# CAN_TO_USART_V2_1.net
KiCad netlist of a schematic drawn in Altium Designer
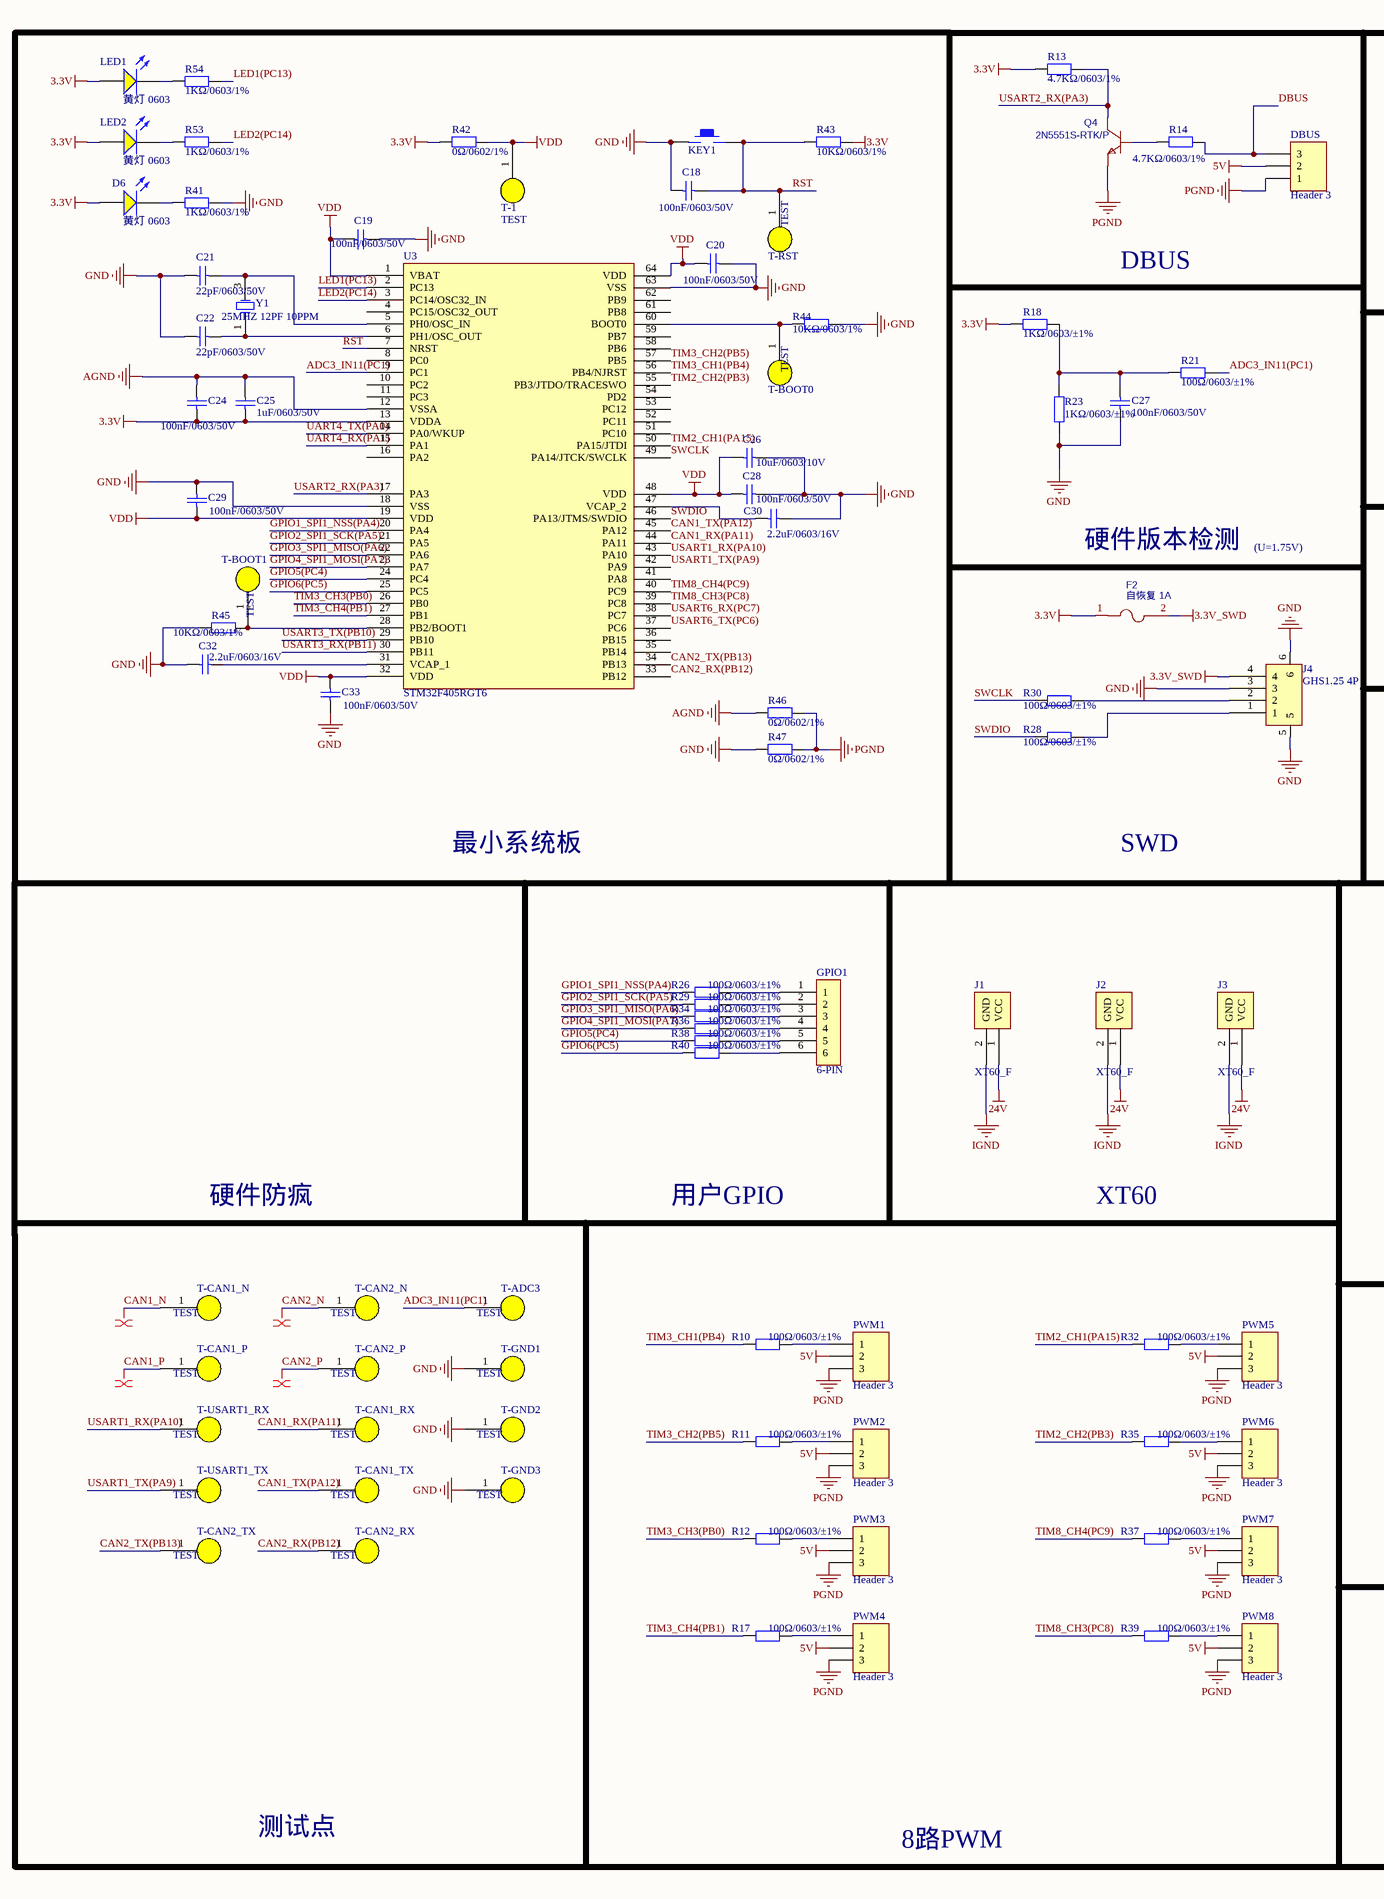
[diagram p0: CAN_TO_USART_V2.1.SchDoc, left]
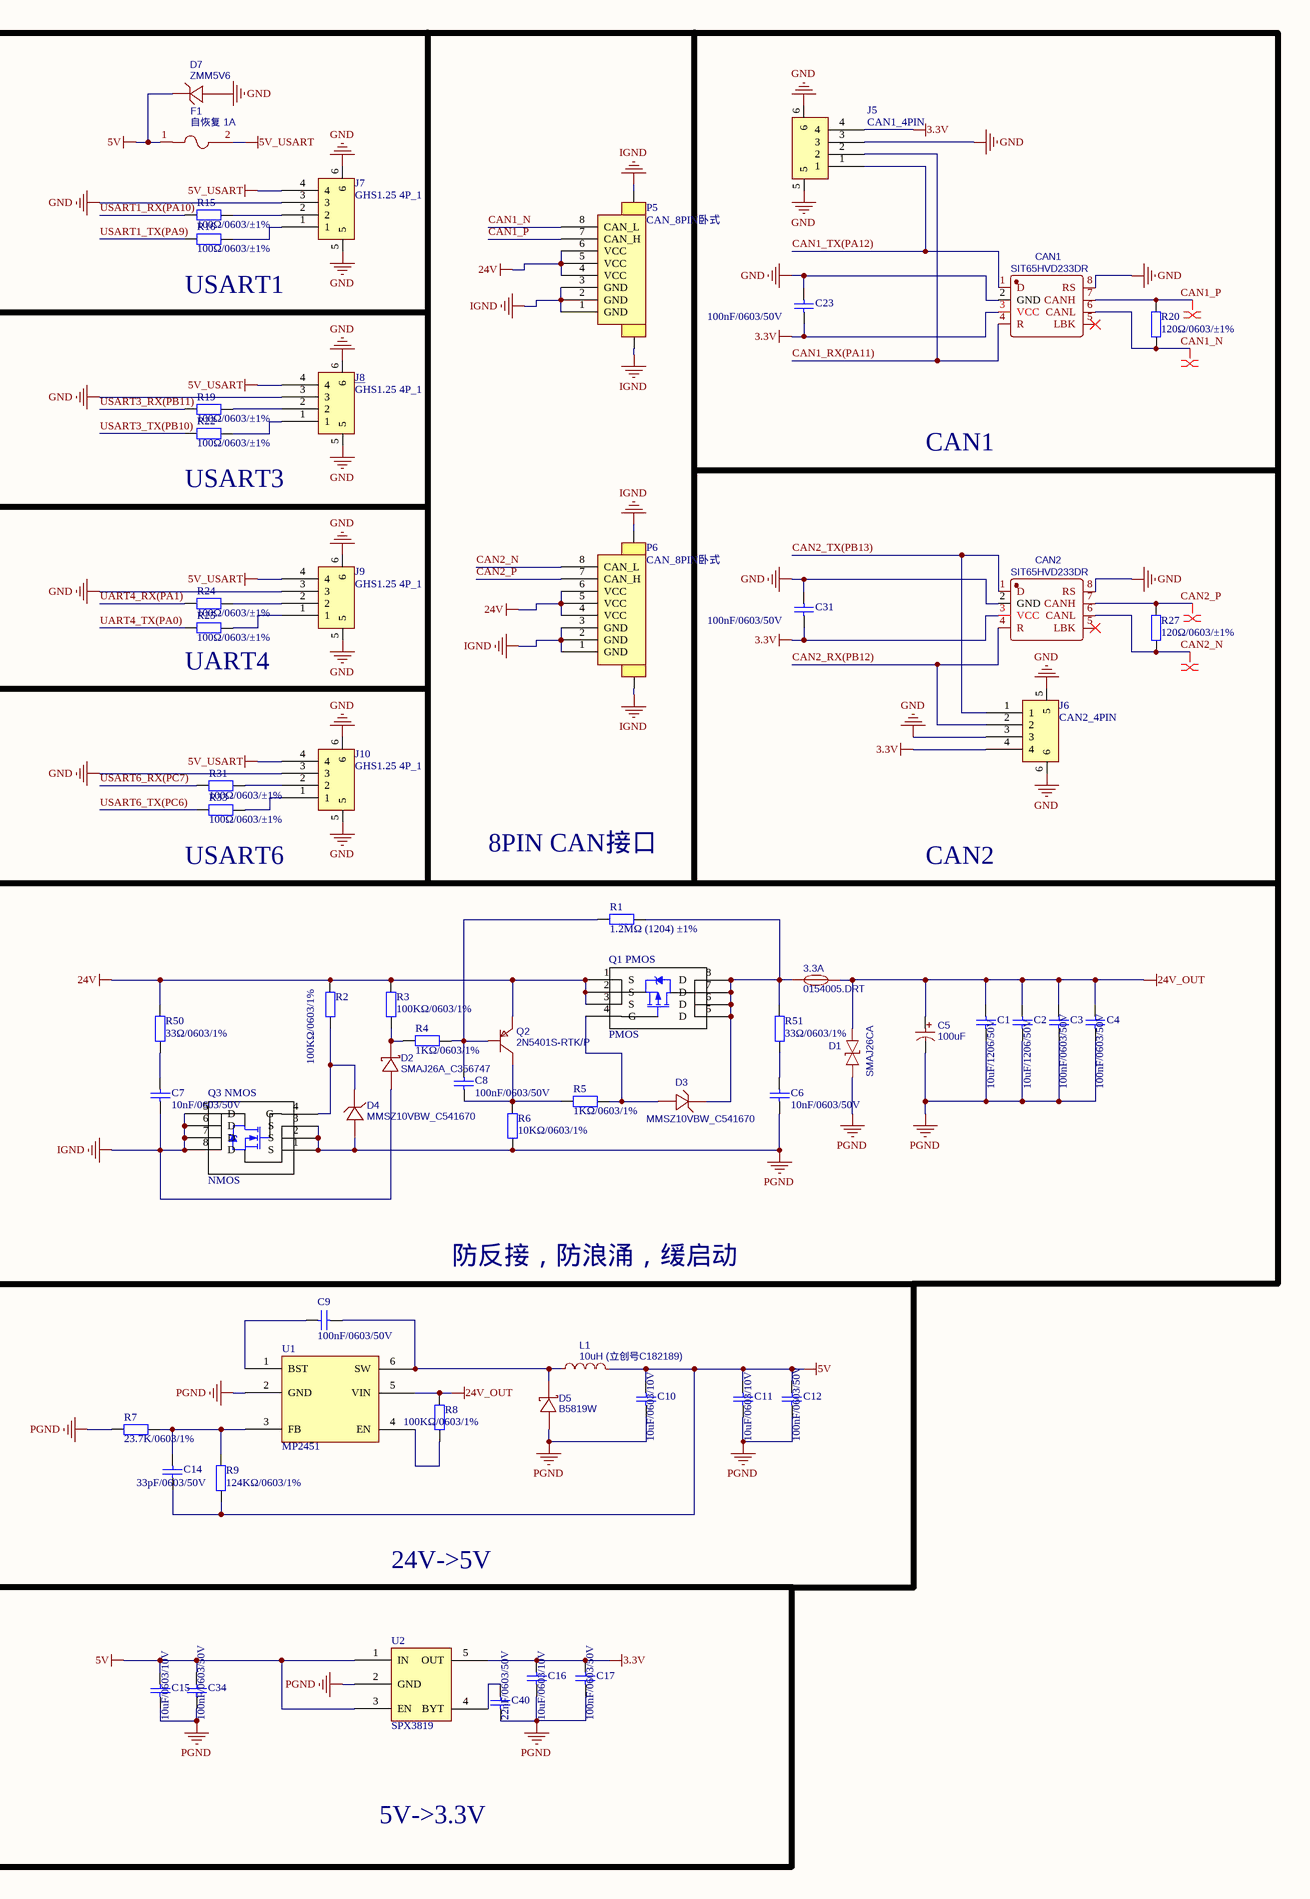
[diagram p1: CAN_TO_USART_V2.1.SchDoc, right]

(export (version "E")
  (design (tool "Eeschema 10.0.6"))
  (components
    (comp (ref "3.3A")
      (value "0154005.DRT")
      (footprint "FUSE 3.3A")
      (fields (field (name "BOM_SUPPLIER PART") "C206917") (field (name "CONTRIBUTOR") "LCSC"))
      (libsource (lib "altium-import") (part "root_0_mirrored_0154005.DRT_"))
    )
    (comp (ref "C1")
      (value "10uF/1206/50V")
      (footprint "1206_C")
      (description "贴片电容")
      (libsource (lib "Miscellaneous Devices LC") (part "1206 10uF (106) 10% 50V"))
    )
    (comp (ref "C2")
      (value "10uF/1206/50V")
      (footprint "1206_C")
      (description "贴片电容")
      (libsource (lib "Miscellaneous Devices LC") (part "1206 10uF (106) 10% 50V"))
    )
    (comp (ref "C3")
      (value "100nF/0603/50V")
      (footprint "0603_C")
      (description "贴片电容")
      (libsource (lib "Miscellaneous Devices LC") (part "0603 100nF (104) 10% 50V"))
    )
    (comp (ref "C4")
      (value "100nF/0603/50V")
      (footprint "0603_C")
      (description "贴片电容")
      (libsource (lib "Miscellaneous Devices LC") (part "0603 100nF (104) 10% 50V"))
    )
    (comp (ref "C5")
      (value "100uF")
      (footprint "100UF E")
      (fields
        (field (name "BOM_MANUFACTURER PART") "50V 100uF 8X12")
        (field (name "BOM_SUPPLIER PART") "C2749")
      )
      (libsource (lib "altium-import") (part "root_3_100uF_"))
    )
    (comp (ref "C6")
      (value "10nF/0603/50V")
      (footprint "0603_C")
      (description "贴片电容")
      (libsource (lib "Miscellaneous Devices LC") (part "0603 10nF (103) 10% 50V"))
    )
    (comp (ref "C7")
      (value "10nF/0603/50V")
      (footprint "0603_C")
      (description "贴片电容")
      (libsource (lib "Miscellaneous Devices LC") (part "0603 10nF (103) 10% 50V"))
    )
    (comp (ref "C8")
      (value "100nF/0603/50V")
      (footprint "0603_C")
      (description "贴片电容")
      (libsource (lib "Miscellaneous Devices LC") (part "0603 100nF (104) 10% 50V"))
    )
    (comp (ref "C9")
      (value "100nF/0603/50V")
      (footprint "0603_C")
      (description "贴片电容")
      (libsource (lib "Miscellaneous Devices LC") (part "0603 100nF (104) 10% 50V"))
    )
    (comp (ref "C10")
      (value "10uF/0603/10V")
      (footprint "0603_C")
      (description "贴片电容")
      (libsource (lib "Miscellaneous Devices LC") (part "0603 10uF (106) 10% 10V"))
    )
    (comp (ref "C11")
      (value "10uF/0603/10V")
      (footprint "0603_C")
      (description "贴片电容")
      (libsource (lib "Miscellaneous Devices LC") (part "0603 10uF (106) 10% 10V"))
    )
    (comp (ref "C12")
      (value "100nF/0603/50V")
      (footprint "0603_C")
      (description "贴片电容")
      (libsource (lib "Miscellaneous Devices LC") (part "0603 100nF (104) 10% 50V"))
    )
    (comp (ref "C14")
      (value "33pF/0603/50V")
      (footprint "0603_C")
      (description "贴片电容")
      (libsource (lib "Miscellaneous Devices LC") (part "0603 33pF (330) 5% 50V"))
    )
    (comp (ref "C15")
      (value "10uF/0603/10V")
      (footprint "0603_C")
      (description "贴片电容")
      (libsource (lib "Miscellaneous Devices LC") (part "0603 10uF (106) 10% 10V"))
    )
    (comp (ref "C16")
      (value "10uF/0603/10V")
      (footprint "0603_C")
      (description "贴片电容")
      (libsource (lib "Miscellaneous Devices LC") (part "0603 10uF (106) 10% 10V"))
    )
    (comp (ref "C17")
      (value "100nF/0603/50V")
      (footprint "0603_C")
      (description "贴片电容")
      (libsource (lib "Miscellaneous Devices LC") (part "0603 100nF (104) 10% 50V"))
    )
    (comp (ref "C18")
      (value "100nF/0603/50V")
      (footprint "0603_C")
      (description "贴片电容")
      (libsource (lib "Miscellaneous Devices LC") (part "0603 100nF (104) 10% 50V"))
    )
    (comp (ref "C19")
      (value "100nF/0603/50V")
      (footprint "0603_C")
      (description "贴片电容")
      (libsource (lib "Miscellaneous Devices LC") (part "0603 100nF (104) 10% 50V"))
    )
    (comp (ref "C20")
      (value "100nF/0603/50V")
      (footprint "0603_C")
      (description "贴片电容")
      (libsource (lib "Miscellaneous Devices LC") (part "0603 100nF (104) 10% 50V"))
    )
    (comp (ref "C21")
      (value "22pF/0603/50V")
      (footprint "0603_C")
      (description "贴片电容")
      (libsource (lib "Miscellaneous Devices LC") (part "0603 22pF (220) 5% 50V"))
    )
    (comp (ref "C22")
      (value "22pF/0603/50V")
      (footprint "0603_C")
      (description "贴片电容")
      (libsource (lib "Miscellaneous Devices LC") (part "0603 22pF (220) 5% 50V"))
    )
    (comp (ref "C23")
      (value "100nF/0603/50V")
      (footprint "0603_C")
      (description "贴片电容")
      (libsource (lib "Miscellaneous Devices LC") (part "0603 100nF (104) 10% 50V"))
    )
    (comp (ref "C24")
      (value "100nF/0603/50V")
      (footprint "0603_C")
      (description "贴片电容")
      (libsource (lib "Miscellaneous Devices LC") (part "0603 100nF (104) 10% 50V"))
    )
    (comp (ref "C25")
      (value "1uF/0603/50V")
      (footprint "0603_C")
      (description "贴片电容")
      (libsource (lib "Miscellaneous Devices LC") (part "0603 1uF (105) 10% 50V"))
    )
    (comp (ref "C26")
      (value "10uF/0603/10V")
      (footprint "0603_C")
      (description "贴片电容")
      (libsource (lib "Miscellaneous Devices LC") (part "0603 10uF (106) 10% 10V"))
    )
    (comp (ref "C27")
      (value "100nF/0603/50V")
      (footprint "0603_C")
      (description "贴片电容")
      (libsource (lib "Miscellaneous Devices LC") (part "0603 100nF (104) 10% 50V"))
    )
    (comp (ref "C28")
      (value "100nF/0603/50V")
      (footprint "0603_C")
      (description "贴片电容")
      (libsource (lib "Miscellaneous Devices LC") (part "0603 100nF (104) 10% 50V"))
    )
    (comp (ref "C29")
      (value "100nF/0603/50V")
      (footprint "0603_C")
      (description "贴片电容")
      (libsource (lib "Miscellaneous Devices LC") (part "0603 100nF (104) 10% 50V"))
    )
    (comp (ref "C30")
      (value "2.2uF/0603/16V")
      (footprint "0603_C")
      (description "贴片电容")
      (libsource (lib "Miscellaneous Devices LC") (part "0603 2.2uF (225) 10% 16V"))
    )
    (comp (ref "C31")
      (value "100nF/0603/50V")
      (footprint "0603_C")
      (description "贴片电容")
      (libsource (lib "Miscellaneous Devices LC") (part "0603 100nF (104) 10% 50V"))
    )
    (comp (ref "C32")
      (value "2.2uF/0603/16V")
      (footprint "0603_C")
      (description "贴片电容")
      (libsource (lib "Miscellaneous Devices LC") (part "0603 2.2uF (225) 10% 16V"))
    )
    (comp (ref "C33")
      (value "100nF/0603/50V")
      (footprint "0603_C")
      (description "贴片电容")
      (libsource (lib "Miscellaneous Devices LC") (part "0603 100nF (104) 10% 50V"))
    )
    (comp (ref "C34")
      (value "100nF/0603/50V")
      (footprint "0603_C")
      (description "贴片电容")
      (libsource (lib "Miscellaneous Devices LC") (part "0603 100nF (104) 10% 50V"))
    )
    (comp (ref "C40")
      (value "22nF/0603/50V")
      (footprint "0603_C")
      (description "贴片电容")
      (libsource (lib "Miscellaneous Devices LC") (part "0603 22nF (223) 10% 50V"))
    )
    (comp (ref "CAN1")
      (value "SIT65HVD233DR")
      (footprint "CAN-MCU")
      (fields (field (name "BOM_SUPPLIER PART") "C496620") (field (name "CONTRIBUTOR") "LCSC"))
      (libsource (lib "altium-import") (part "root_0_SIT65HVD233DR_"))
    )
    (comp (ref "CAN2")
      (value "SIT65HVD233DR")
      (footprint "CAN-MCU")
      (fields (field (name "BOM_SUPPLIER PART") "C496620") (field (name "CONTRIBUTOR") "LCSC"))
      (libsource (lib "altium-import") (part "root_0_SIT65HVD233DR_"))
    )
    (comp (ref "D1")
      (value "SMAJ26CA")
      (footprint "SMAJ26CA")
      (fields (field (name "BOM_SUPPLIER PART") "C353459") (field (name "CONTRIBUTOR") "LCSC"))
      (libsource (lib "altium-import") (part "root_1_SMAJ26CA_C353459_"))
    )
    (comp (ref "D2")
      (value "SMAJ26A_C356747")
      (footprint "SMA_L4.4-W2.8-LS5.4-RD")
      (fields
        (field (name "BOM_SUPPLIER PART") "C356747")
        (field (name "BOM_MANUFACTURER PART") "SMAJ26A")
        (field (name "CONTRIBUTOR") "LCSC")
      )
      (libsource (lib "altium-import") (part "root_3_SMAJ26A_C356747_"))
    )
    (comp (ref "D3")
      (value "MMSZ10VBW_C541670")
      (footprint "SOD-123_L2.7-W1.6-LS3.7-RD")
      (fields
        (field (name "BOM_SUPPLIER PART") "C541670")
        (field (name "BOM_MANUFACTURER PART") "MMSZ10VBW")
        (field (name "CONTRIBUTOR") "LCSC")
      )
      (libsource (lib "altium-import") (part "root_2_MMSZ10VBW_C541670_"))
    )
    (comp (ref "D4")
      (value "MMSZ10VBW_C541670")
      (footprint "SOD-123_L2.7-W1.6-LS3.7-RD")
      (fields
        (field (name "BOM_SUPPLIER PART") "C541670")
        (field (name "BOM_MANUFACTURER PART") "MMSZ10VBW")
        (field (name "CONTRIBUTOR") "LCSC")
      )
      (libsource (lib "altium-import") (part "root_3_MMSZ10VBW_C541670_"))
    )
    (comp (ref "D5")
      (value "B5819W")
      (footprint "SOD-123_L2.8-W1.8-LS3.7-RD")
      (fields (field (name "BOM_SUPPLIER PART") "C64885"))
      (libsource (lib "altium-import") (part "root_3_B5819W_"))
    )
    (comp (ref "D6")
      (value "黄灯 0603")
      (footprint "0603_LED_S1")
      (description "发光二极管")
      (libsource (lib "Miscellaneous Devices LC") (part "0603 黄灯"))
    )
    (comp (ref "D7")
      (value "ZMM5V6")
      (footprint "ZMM5.6V")
      (fields (field (name "BOM_SUPPLIER PART") "C8062"))
      (libsource (lib "altium-import") (part "root_0_ZMM5V6_"))
    )
    (comp (ref "DBUS")
      (value "Header 3")
      (footprint "HDR1X3")
      (description "Header, 3-Pin")
      (fields (field (name "PUBLISHER") "Altium Limited"))
      (libsource (lib "") (part "Header 3_1"))
    )
    (comp (ref "F1")
      (value "自恢复 1A")
      (footprint "1A 0805")
      (fields
        (field (name "BOM_MANUFACTURER PART") "ASMD1206-100")
        (field (name "BOM_SUPPLIER PART") "C135340")
        (field (name "CONTRIBUTOR") "LCSC")
      )
      (libsource (lib "altium-import") (part "root_0_ASMD1206-100_"))
    )
    (comp (ref "F2")
      (value "自恢复 1A")
      (footprint "1A 0805")
      (fields
        (field (name "BOM_MANUFACTURER PART") "ASMD1206-100")
        (field (name "BOM_SUPPLIER PART") "C135340")
        (field (name "CONTRIBUTOR") "LCSC")
      )
      (libsource (lib "altium-import") (part "root_0_ASMD1206-100_"))
    )
    (comp (ref "GPIO1") (value "6-PIN") (footprint "6P") (libsource (lib "Chassis_Con") (part "6-PIN")))
    (comp (ref "J1")
      (value "XT60_F")
      (footprint "RobotLab_Common_Used:XT60_F（立式）")
      (libsource (lib "RobotLab_Common_Used") (part "XT60_F"))
    )
    (comp (ref "J2")
      (value "XT60_F")
      (footprint "RobotLab_Common_Used:XT60_F（立式）")
      (libsource (lib "RobotLab_Common_Used") (part "XT60_F"))
    )
    (comp (ref "J3")
      (value "XT60_F")
      (footprint "RobotLab_Common_Used:XT60_F（立式）")
      (libsource (lib "RobotLab_Common_Used") (part "XT60_F"))
    )
    (comp (ref "J4")
      (value "GHS1.25 4P")
      (footprint "RobotLab_Common_Used:SM04B-GHS立式")
      (description "立式")
      (libsource (lib "RobotLab_Common_Used") (part "GHS1.25 4P"))
    )
    (comp (ref "J5")
      (value "CAN1_4PIN")
      (footprint "RobotLab_Common_Used:SM04B-GHS卧式")
      (description "卧式短边")
      (libsource (lib "") (part "GHS1.25 4P_1_2"))
    )
    (comp (ref "J6")
      (value "CAN2_4PIN")
      (footprint "RobotLab_Common_Used:SM04B-GHS卧式")
      (description "卧式短边")
      (libsource (lib "") (part "GHS1.25 4P_1_1"))
    )
    (comp (ref "J7")
      (value "GHS1.25 4P_1")
      (footprint "RobotLab_Common_Used:SM04B-GHS卧式")
      (description "卧式短边")
      (libsource (lib "RobotLab_Common_Used") (part "GHS1.25 4P_1"))
    )
    (comp (ref "J8")
      (value "GHS1.25 4P_1")
      (footprint "RobotLab_Common_Used:SM04B-GHS卧式")
      (description "卧式短边")
      (libsource (lib "RobotLab_Common_Used") (part "GHS1.25 4P_1"))
    )
    (comp (ref "J9")
      (value "GHS1.25 4P_1")
      (footprint "RobotLab_Common_Used:SM04B-GHS卧式")
      (description "卧式短边")
      (libsource (lib "RobotLab_Common_Used") (part "GHS1.25 4P_1"))
    )
    (comp (ref "J10")
      (value "GHS1.25 4P_1")
      (footprint "RobotLab_Common_Used:SM04B-GHS卧式")
      (description "卧式短边")
      (libsource (lib "RobotLab_Common_Used") (part "GHS1.25 4P_1"))
    )
    (comp (ref "KEY1") (value "KEY_M") (footprint "KEY") (libsource (lib "MiniSTM32 V3.0封装库") (part "KEY_M")))
    (comp (ref "L1")
      (value "10uH (立创号C182189)")
      (footprint "10UH 1A")
      (fields
        (field (name "BOM_SUPPLIER PART") "C182189")
        (field (name "BOM_MANUFACTURER PART") "SLW5040S100MST")
        (field (name "CONTRIBUTOR") "LCSC")
      )
      (libsource (lib "altium-import") (part "root_0_10uH_"))
    )
    (comp (ref "LED1")
      (value "黄灯 0603")
      (footprint "0603_LED_S1")
      (description "发光二极管")
      (libsource (lib "Miscellaneous Devices LC") (part "0603 黄灯"))
    )
    (comp (ref "LED2")
      (value "黄灯 0603")
      (footprint "0603_LED_S1")
      (description "发光二极管")
      (libsource (lib "Miscellaneous Devices LC") (part "0603 黄灯"))
    )
    (comp (ref "P5")
      (value "CAN_8PIN卧式")
      (footprint "RobotLab_Common_Used:8Pin")
      (description "卧式")
      (libsource (lib "RobotLab_Common_Used") (part "CAN_8PIN"))
    )
    (comp (ref "P6")
      (value "CAN_8PIN卧式")
      (footprint "RobotLab_Common_Used:8Pin")
      (description "卧式")
      (libsource (lib "RobotLab_Common_Used") (part "CAN_8PIN"))
    )
    (comp (ref "PWM1")
      (value "Header 3")
      (footprint "HDR1X3")
      (description "Header, 3-Pin")
      (fields (field (name "PUBLISHER") "Altium Limited"))
      (libsource (lib "Miscellaneous Connectors") (part "Header 3"))
    )
    (comp (ref "PWM2")
      (value "Header 3")
      (footprint "HDR1X3")
      (description "Header, 3-Pin")
      (fields (field (name "PUBLISHER") "Altium Limited"))
      (libsource (lib "Miscellaneous Connectors") (part "Header 3"))
    )
    (comp (ref "PWM3")
      (value "Header 3")
      (footprint "HDR1X3")
      (description "Header, 3-Pin")
      (fields (field (name "PUBLISHER") "Altium Limited"))
      (libsource (lib "Miscellaneous Connectors") (part "Header 3"))
    )
    (comp (ref "PWM4")
      (value "Header 3")
      (footprint "HDR1X3")
      (description "Header, 3-Pin")
      (fields (field (name "PUBLISHER") "Altium Limited"))
      (libsource (lib "Miscellaneous Connectors") (part "Header 3"))
    )
    (comp (ref "PWM5")
      (value "Header 3")
      (footprint "HDR1X3")
      (description "Header, 3-Pin")
      (fields (field (name "PUBLISHER") "Altium Limited"))
      (libsource (lib "Miscellaneous Connectors") (part "Header 3"))
    )
    (comp (ref "PWM6")
      (value "Header 3")
      (footprint "HDR1X3")
      (description "Header, 3-Pin")
      (fields (field (name "PUBLISHER") "Altium Limited"))
      (libsource (lib "Miscellaneous Connectors") (part "Header 3"))
    )
    (comp (ref "PWM7")
      (value "Header 3")
      (footprint "HDR1X3")
      (description "Header, 3-Pin")
      (fields (field (name "PUBLISHER") "Altium Limited"))
      (libsource (lib "Miscellaneous Connectors") (part "Header 3"))
    )
    (comp (ref "PWM8")
      (value "Header 3")
      (footprint "HDR1X3")
      (description "Header, 3-Pin")
      (fields (field (name "PUBLISHER") "Altium Limited"))
      (libsource (lib "Miscellaneous Connectors") (part "Header 3"))
    )
    (comp (ref "Q1 PMOS")
      (value "PMOS")
      (footprint "PMOS TCPA8123")
      (fields (field (name "PUBLISHER") "Altium Limited"))
      (libsource (lib "CAN_TO_USART") (part "PMOS 8PIN"))
    )
    (comp (ref "Q2")
      (value "2N5401S-RTK/P")
      (footprint "SOT-23-3_L2.9-W1.6-P1.90-LS2.8-TR-CW")
      (fields (field (name "BOM_SUPPLIER PART") "C147293") (field (name "CONTRIBUTOR") "LCSC"))
      (libsource (lib "altium-import") (part "root_2_mirrored_2N5401S-RTK/P_"))
    )
    (comp (ref "Q3 NMOS")
      (value "NMOS")
      (footprint "NMOS")
      (fields (field (name "PUBLISHER") "Altium Limited"))
      (libsource (lib "CAN_TO_USART") (part "NMOS 8PIN"))
    )
    (comp (ref "Q4")
      (value "2N5551S-RTK/P")
      (footprint "SOT-23-3_L2.9-W1.6-P1.90-LS2.8-TR-CW")
      (fields (field (name "BOM_SUPPLIER PART") "C112669") (field (name "CONTRIBUTOR") "LCSC"))
      (libsource (lib "altium-import") (part "root_0_mirrored_2N5551S-RTK/P_"))
    )
    (comp (ref "R1")
      (value "1.2MΩ (1204) ±1%")
      (footprint "0603_R")
      (description "贴片电阻")
      (libsource (lib "Miscellaneous Devices LC") (part "0603 1.2MΩ (1204) 1%"))
    )
    (comp (ref "R2")
      (value "100KΩ/0603/1%")
      (footprint "0603_R")
      (description "贴片电阻")
      (libsource (lib "Miscellaneous Devices LC") (part "0603 100KΩ (1003) 1%"))
    )
    (comp (ref "R3")
      (value "100KΩ/0603/1%")
      (footprint "0603_R")
      (description "贴片电阻")
      (libsource (lib "") (part "0603 100KΩ (1003) 1%_1"))
    )
    (comp (ref "R4")
      (value "1KΩ/0603/1%")
      (footprint "0603_R")
      (description "贴片电阻")
      (libsource (lib "Miscellaneous Devices LC") (part "0603 1KΩ (1001) 1%"))
    )
    (comp (ref "R5")
      (value "1KΩ/0603/1%")
      (footprint "0603_R")
      (description "贴片电阻")
      (libsource (lib "Miscellaneous Devices LC") (part "0603 1KΩ (1001) 1%"))
    )
    (comp (ref "R6")
      (value "10KΩ/0603/1%")
      (footprint "0603_R")
      (description "贴片电阻")
      (libsource (lib "") (part "0603 10KΩ (1002) 1%_1"))
    )
    (comp (ref "R7")
      (value "23.7K/0603/1%")
      (footprint "0603_R")
      (description "贴片电阻")
      (libsource (lib "Miscellaneous Devices LC") (part "0603 3KΩ (3001) 1%"))
    )
    (comp (ref "R8")
      (value "100KΩ/0603/1%")
      (footprint "0603_R")
      (description "贴片电阻")
      (libsource (lib "Miscellaneous Devices LC") (part "0603 100KΩ (1003) 1%"))
    )
    (comp (ref "R9")
      (value "124KΩ/0603/1%")
      (footprint "0603_R")
      (description "贴片电阻")
      (libsource (lib "") (part "0603 3KΩ (3001) 1%_1"))
    )
    (comp (ref "R10")
      (value "100Ω/0603/±1%")
      (footprint "0603_R")
      (description "贴片电阻")
      (libsource (lib "Miscellaneous Devices LC") (part "0603 100Ω (1000) 1%"))
    )
    (comp (ref "R11")
      (value "100Ω/0603/±1%")
      (footprint "0603_R")
      (description "贴片电阻")
      (libsource (lib "Miscellaneous Devices LC") (part "0603 100Ω (1000) 1%"))
    )
    (comp (ref "R12")
      (value "100Ω/0603/±1%")
      (footprint "0603_R")
      (description "贴片电阻")
      (libsource (lib "Miscellaneous Devices LC") (part "0603 100Ω (1000) 1%"))
    )
    (comp (ref "R13")
      (value "4.7KΩ/0603/1%")
      (footprint "0603_R")
      (description "贴片电阻")
      (libsource (lib "Miscellaneous Devices LC") (part "0603 4.7KΩ (4701) 1%"))
    )
    (comp (ref "R14")
      (value "4.7KΩ/0603/1%")
      (footprint "0603_R")
      (description "贴片电阻")
      (libsource (lib "Miscellaneous Devices LC") (part "0603 4.7KΩ (4701) 1%"))
    )
    (comp (ref "R15")
      (value "100Ω/0603/±1%")
      (footprint "0603_R")
      (description "贴片电阻")
      (libsource (lib "Miscellaneous Devices LC") (part "0603 100Ω (1000) 1%"))
    )
    (comp (ref "R16")
      (value "100Ω/0603/±1%")
      (footprint "0603_R")
      (description "贴片电阻")
      (libsource (lib "Miscellaneous Devices LC") (part "0603 100Ω (1000) 1%"))
    )
    (comp (ref "R17")
      (value "100Ω/0603/±1%")
      (footprint "0603_R")
      (description "贴片电阻")
      (libsource (lib "Miscellaneous Devices LC") (part "0603 100Ω (1000) 1%"))
    )
    (comp (ref "R18")
      (value "1KΩ/0603/±1%")
      (footprint "0603_R")
      (description "贴片电阻")
      (libsource (lib "Miscellaneous Devices LC") (part "0603 1MΩ (1004) 1%"))
    )
    (comp (ref "R19")
      (value "100Ω/0603/±1%")
      (footprint "0603_R")
      (description "贴片电阻")
      (libsource (lib "Miscellaneous Devices LC") (part "0603 100Ω (1000) 1%"))
    )
    (comp (ref "R20")
      (value "120Ω/0603/±1%")
      (footprint "0603_R")
      (description "贴片电阻")
      (libsource (lib "Miscellaneous Devices LC") (part "0603 120Ω (1200) 1%"))
    )
    (comp (ref "R21")
      (value "100Ω/0603/±1%")
      (footprint "0603_R")
      (description "贴片电阻")
      (libsource (lib "Miscellaneous Devices LC") (part "0603 100Ω (1000) 1%"))
    )
    (comp (ref "R22")
      (value "100Ω/0603/±1%")
      (footprint "0603_R")
      (description "贴片电阻")
      (libsource (lib "Miscellaneous Devices LC") (part "0603 100Ω (1000) 1%"))
    )
    (comp (ref "R23")
      (value "1KΩ/0603/±1%")
      (footprint "0603_R")
      (description "贴片电阻")
      (libsource (lib "") (part "0603 1KΩ (1001) 1%_1"))
    )
    (comp (ref "R24")
      (value "100Ω/0603/±1%")
      (footprint "0603_R")
      (description "贴片电阻")
      (libsource (lib "Miscellaneous Devices LC") (part "0603 100Ω (1000) 1%"))
    )
    (comp (ref "R25")
      (value "100Ω/0603/±1%")
      (footprint "0603_R")
      (description "贴片电阻")
      (libsource (lib "Miscellaneous Devices LC") (part "0603 100Ω (1000) 1%"))
    )
    (comp (ref "R26")
      (value "100Ω/0603/±1%")
      (footprint "0603_R")
      (description "贴片电阻")
      (libsource (lib "Miscellaneous Devices LC") (part "0603 100Ω (1000) 1%"))
    )
    (comp (ref "R27")
      (value "120Ω/0603/±1%")
      (footprint "0603_R")
      (description "贴片电阻")
      (libsource (lib "Miscellaneous Devices LC") (part "0603 120Ω (1200) 1%"))
    )
    (comp (ref "R28")
      (value "100Ω/0603/±1%")
      (footprint "0603_R")
      (description "贴片电阻")
      (libsource (lib "Miscellaneous Devices LC") (part "0603 100Ω (1000) 1%"))
    )
    (comp (ref "R29")
      (value "100Ω/0603/±1%")
      (footprint "0603_R")
      (description "贴片电阻")
      (libsource (lib "Miscellaneous Devices LC") (part "0603 100Ω (1000) 1%"))
    )
    (comp (ref "R30")
      (value "100Ω/0603/±1%")
      (footprint "0603_R")
      (description "贴片电阻")
      (libsource (lib "Miscellaneous Devices LC") (part "0603 100Ω (1000) 1%"))
    )
    (comp (ref "R31")
      (value "100Ω/0603/±1%")
      (footprint "0603_R")
      (description "贴片电阻")
      (libsource (lib "Miscellaneous Devices LC") (part "0603 100Ω (1000) 1%"))
    )
    (comp (ref "R32")
      (value "100Ω/0603/±1%")
      (footprint "0603_R")
      (description "贴片电阻")
      (libsource (lib "Miscellaneous Devices LC") (part "0603 100Ω (1000) 1%"))
    )
    (comp (ref "R33")
      (value "100Ω/0603/±1%")
      (footprint "0603_R")
      (description "贴片电阻")
      (libsource (lib "Miscellaneous Devices LC") (part "0603 100Ω (1000) 1%"))
    )
    (comp (ref "R34")
      (value "100Ω/0603/±1%")
      (footprint "0603_R")
      (description "贴片电阻")
      (libsource (lib "Miscellaneous Devices LC") (part "0603 100Ω (1000) 1%"))
    )
    (comp (ref "R35")
      (value "100Ω/0603/±1%")
      (footprint "0603_R")
      (description "贴片电阻")
      (libsource (lib "Miscellaneous Devices LC") (part "0603 100Ω (1000) 1%"))
    )
    (comp (ref "R36")
      (value "100Ω/0603/±1%")
      (footprint "0603_R")
      (description "贴片电阻")
      (libsource (lib "Miscellaneous Devices LC") (part "0603 100Ω (1000) 1%"))
    )
    (comp (ref "R37")
      (value "100Ω/0603/±1%")
      (footprint "0603_R")
      (description "贴片电阻")
      (libsource (lib "Miscellaneous Devices LC") (part "0603 100Ω (1000) 1%"))
    )
    (comp (ref "R38")
      (value "100Ω/0603/±1%")
      (footprint "0603_R")
      (description "贴片电阻")
      (libsource (lib "Miscellaneous Devices LC") (part "0603 100Ω (1000) 1%"))
    )
    (comp (ref "R39")
      (value "100Ω/0603/±1%")
      (footprint "0603_R")
      (description "贴片电阻")
      (libsource (lib "Miscellaneous Devices LC") (part "0603 100Ω (1000) 1%"))
    )
    (comp (ref "R40")
      (value "100Ω/0603/±1%")
      (footprint "0603_R")
      (description "贴片电阻")
      (libsource (lib "Miscellaneous Devices LC") (part "0603 100Ω (1000) 1%"))
    )
    (comp (ref "R41")
      (value "1KΩ/0603/1%")
      (footprint "0603_R")
      (description "贴片电阻")
      (libsource (lib "Miscellaneous Devices LC") (part "0603 1KΩ (1001) 1%"))
    )
    (comp (ref "R42")
      (value "0Ω/0602/1%")
      (footprint "0603_R")
      (description "贴片电阻")
      (libsource (lib "Miscellaneous Devices LC") (part "0603 0Ω (0R0) 1%"))
    )
    (comp (ref "R43")
      (value "10KΩ/0603/1%")
      (footprint "0603_R")
      (description "贴片电阻")
      (libsource (lib "Miscellaneous Devices LC") (part "0603 10KΩ (1002) 1%"))
    )
    (comp (ref "R44")
      (value "10KΩ/0603/1%")
      (footprint "0603_R")
      (description "贴片电阻")
      (libsource (lib "Miscellaneous Devices LC") (part "0603 10KΩ (1002) 1%"))
    )
    (comp (ref "R45")
      (value "10KΩ/0603/1%")
      (footprint "0603_R")
      (description "贴片电阻")
      (libsource (lib "Miscellaneous Devices LC") (part "0603 10KΩ (1002) 1%"))
    )
    (comp (ref "R46")
      (value "0Ω/0602/1%")
      (footprint "0603_R")
      (description "贴片电阻")
      (libsource (lib "Miscellaneous Devices LC") (part "0603 0Ω (0R0) 1%"))
    )
    (comp (ref "R47")
      (value "0Ω/0602/1%")
      (footprint "0603_R")
      (description "贴片电阻")
      (libsource (lib "Miscellaneous Devices LC") (part "0603 0Ω (0R0) 1%"))
    )
    (comp (ref "R50")
      (value "33Ω/0603/1%")
      (footprint "0603_R")
      (description "贴片电阻")
      (libsource (lib "Miscellaneous Devices LC") (part "0603 33Ω (33R0) 1%"))
    )
    (comp (ref "R51")
      (value "33Ω/0603/1%")
      (footprint "0603_R")
      (description "贴片电阻")
      (libsource (lib "Miscellaneous Devices LC") (part "0603 33Ω (33R0) 1%"))
    )
    (comp (ref "R53")
      (value "1KΩ/0603/1%")
      (footprint "0603_R")
      (description "贴片电阻")
      (libsource (lib "Miscellaneous Devices LC") (part "0603 1KΩ (1001) 1%"))
    )
    (comp (ref "R54")
      (value "1KΩ/0603/1%")
      (footprint "0603_R")
      (description "贴片电阻")
      (libsource (lib "Miscellaneous Devices LC") (part "0603 1KΩ (1001) 1%"))
    )
    (comp (ref "T-1") (value "TEST") (footprint "TEST-POINT") (libsource (lib "CAN_TO_USART") (part "TEST")))
    (comp (ref "T-ADC3")
      (value "TEST")
      (footprint "TEST-POINT")
      (libsource (lib "CAN_TO_USART") (part "TEST"))
    )
    (comp (ref "T-BOOT0")
      (value "TEST")
      (footprint "TEST-POINT")
      (libsource (lib "CAN_TO_USART") (part "TEST"))
    )
    (comp (ref "T-BOOT1")
      (value "TEST")
      (footprint "TEST-POINT")
      (libsource (lib "CAN_TO_USART") (part "TEST"))
    )
    (comp (ref "T-CAN1_N")
      (value "TEST")
      (footprint "TEST-POINT")
      (libsource (lib "CAN_TO_USART") (part "TEST"))
    )
    (comp (ref "T-CAN1_P")
      (value "TEST")
      (footprint "TEST-POINT")
      (libsource (lib "CAN_TO_USART") (part "TEST"))
    )
    (comp (ref "T-CAN1_RX")
      (value "TEST")
      (footprint "TEST-POINT")
      (libsource (lib "CAN_TO_USART") (part "TEST"))
    )
    (comp (ref "T-CAN1_TX")
      (value "TEST")
      (footprint "TEST-POINT")
      (libsource (lib "CAN_TO_USART") (part "TEST"))
    )
    (comp (ref "T-CAN2_N")
      (value "TEST")
      (footprint "TEST-POINT")
      (libsource (lib "CAN_TO_USART") (part "TEST"))
    )
    (comp (ref "T-CAN2_P")
      (value "TEST")
      (footprint "TEST-POINT")
      (libsource (lib "CAN_TO_USART") (part "TEST"))
    )
    (comp (ref "T-CAN2_RX")
      (value "TEST")
      (footprint "TEST-POINT")
      (libsource (lib "CAN_TO_USART") (part "TEST"))
    )
    (comp (ref "T-CAN2_TX")
      (value "TEST")
      (footprint "TEST-POINT")
      (libsource (lib "CAN_TO_USART") (part "TEST"))
    )
    (comp (ref "T-GND1")
      (value "TEST")
      (footprint "TEST-POINT")
      (libsource (lib "CAN_TO_USART") (part "TEST"))
    )
    (comp (ref "T-GND2")
      (value "TEST")
      (footprint "TEST-POINT")
      (libsource (lib "CAN_TO_USART") (part "TEST"))
    )
    (comp (ref "T-GND3")
      (value "TEST")
      (footprint "TEST-POINT")
      (libsource (lib "CAN_TO_USART") (part "TEST"))
    )
    (comp (ref "T-RST")
      (value "TEST")
      (footprint "TEST-POINT")
      (libsource (lib "CAN_TO_USART") (part "TEST"))
    )
    (comp (ref "T-USART1_RX")
      (value "TEST")
      (footprint "TEST-POINT")
      (libsource (lib "CAN_TO_USART") (part "TEST"))
    )
    (comp (ref "T-USART1_TX")
      (value "TEST")
      (footprint "TEST-POINT")
      (libsource (lib "CAN_TO_USART") (part "TEST"))
    )
    (comp (ref "U1") (value "MP2451") (footprint "MP2451") (libsource (lib "CAN_TO_USART") (part "MP2451")))
    (comp (ref "U2")
      (value "SPX3819")
      (footprint "SPX3819")
      (libsource (lib "CAN_TO_USART") (part "SPX3819"))
    )
    (comp (ref "U3")
      (value "STM32F405RGT6")
      (footprint "STM32F405RGT6")
      (libsource (lib "Chassis_Con") (part "STM32F405RGT6"))
    )
    (comp (ref "Y1")
      (value "25MHZ 12PF 10PPM")
      (footprint "SMD-3225_4P")
      (description "贴片晶振")
      (libsource (lib "Miscellaneous Devices LC") (part "SMD-3225_4P  25MHZ 12PF 10PPM"))
    )
  )
  (nets
    (net (code "1") (name "/ADC3_IN11(PC1)") (class "Default")
      (node (ref "R21") (pin "2") (pinfunction "2_2") (pintype "passive"))
      (node (ref "T-ADC3") (pin "1") (pintype "passive"))
      (node (ref "U3") (pin "9") (pinfunction "PC1_9") (pintype "passive"))
    )
    (net (code "2") (name "/CAN1_N") (class "Default")
      (node (ref "CAN1") (pin "6") (pinfunction "CANL_6") (pintype "passive"))
      (node (ref "P5") (pin "8") (pinfunction "CAN_L_8") (pintype "passive"))
      (node (ref "R20") (pin "1") (pinfunction "1_1") (pintype "passive"))
      (node (ref "T-CAN1_N") (pin "1") (pintype "passive"))
    )
    (net (code "3") (name "/CAN1_P") (class "Default")
      (node (ref "CAN1") (pin "7") (pinfunction "CANH_7") (pintype "passive"))
      (node (ref "P5") (pin "7") (pinfunction "CAN_H_7") (pintype "passive"))
      (node (ref "R20") (pin "2") (pinfunction "2_2") (pintype "passive"))
      (node (ref "T-CAN1_P") (pin "1") (pintype "passive"))
    )
    (net (code "4") (name "/CAN1_RX(PA11)") (class "Default")
      (node (ref "CAN1") (pin "4") (pinfunction "R_4") (pintype "passive"))
      (node (ref "J5") (pin "2") (pinfunction "2_2") (pintype "passive"))
      (node (ref "T-CAN1_RX") (pin "1") (pintype "passive"))
      (node (ref "U3") (pin "44") (pinfunction "PA11_44") (pintype "passive"))
    )
    (net (code "5") (name "/CAN1_TX(PA12)") (class "Default")
      (node (ref "CAN1") (pin "1") (pinfunction "D_1") (pintype "passive"))
      (node (ref "J5") (pin "1") (pinfunction "1_1") (pintype "passive"))
      (node (ref "T-CAN1_TX") (pin "1") (pintype "passive"))
      (node (ref "U3") (pin "45") (pinfunction "PA12_45") (pintype "passive"))
    )
    (net (code "6") (name "/CAN2_N") (class "Default")
      (node (ref "CAN2") (pin "6") (pinfunction "CANL_6") (pintype "passive"))
      (node (ref "P6") (pin "8") (pinfunction "CAN_L_8") (pintype "passive"))
      (node (ref "R27") (pin "1") (pinfunction "1_1") (pintype "passive"))
      (node (ref "T-CAN2_N") (pin "1") (pintype "passive"))
    )
    (net (code "7") (name "/CAN2_P") (class "Default")
      (node (ref "CAN2") (pin "7") (pinfunction "CANH_7") (pintype "passive"))
      (node (ref "P6") (pin "7") (pinfunction "CAN_H_7") (pintype "passive"))
      (node (ref "R27") (pin "2") (pinfunction "2_2") (pintype "passive"))
      (node (ref "T-CAN2_P") (pin "1") (pintype "passive"))
    )
    (net (code "8") (name "/CAN2_RX(PB12)") (class "Default")
      (node (ref "CAN2") (pin "4") (pinfunction "R_4") (pintype "passive"))
      (node (ref "J6") (pin "2") (pinfunction "2_2") (pintype "passive"))
      (node (ref "T-CAN2_RX") (pin "1") (pintype "passive"))
      (node (ref "U3") (pin "33") (pinfunction "PB12_33") (pintype "passive"))
    )
    (net (code "9") (name "/CAN2_TX(PB13)") (class "Default")
      (node (ref "CAN2") (pin "1") (pinfunction "D_1") (pintype "passive"))
      (node (ref "J6") (pin "1") (pinfunction "1_1") (pintype "passive"))
      (node (ref "T-CAN2_TX") (pin "1") (pintype "passive"))
      (node (ref "U3") (pin "34") (pinfunction "PB13_34") (pintype "passive"))
    )
    (net (code "10") (name "/DBUS") (class "Default")
      (node (ref "DBUS") (pin "3") (pinfunction "3_3") (pintype "passive"))
      (node (ref "R14") (pin "2") (pinfunction "2_2") (pintype "passive"))
    )
    (net (code "11") (name "/GPIO1_SPI1_NSS(PA4)") (class "Default")
      (node (ref "R26") (pin "1") (pinfunction "1_1") (pintype "passive"))
      (node (ref "U3") (pin "20") (pinfunction "PA4_20") (pintype "passive"))
    )
    (net (code "12") (name "/GPIO2_SPI1_SCK(PA5)") (class "Default")
      (node (ref "R29") (pin "1") (pinfunction "1_1") (pintype "passive"))
      (node (ref "U3") (pin "21") (pinfunction "PA5_21") (pintype "passive"))
    )
    (net (code "13") (name "/GPIO3_SPI1_MISO(PA6)") (class "Default")
      (node (ref "R34") (pin "1") (pinfunction "1_1") (pintype "passive"))
      (node (ref "U3") (pin "22") (pinfunction "PA6_22") (pintype "passive"))
    )
    (net (code "14") (name "/GPIO4_SPI1_MOSI(PA7)") (class "Default")
      (node (ref "R36") (pin "1") (pinfunction "1_1") (pintype "passive"))
      (node (ref "U3") (pin "23") (pinfunction "PA7_23") (pintype "passive"))
    )
    (net (code "15") (name "/GPIO5(PC4)") (class "Default")
      (node (ref "R38") (pin "1") (pinfunction "1_1") (pintype "passive"))
      (node (ref "U3") (pin "24") (pinfunction "PC4_24") (pintype "passive"))
    )
    (net (code "16") (name "/GPIO6(PC5)") (class "Default")
      (node (ref "R40") (pin "1") (pinfunction "1_1") (pintype "passive"))
      (node (ref "U3") (pin "25") (pinfunction "PC5_25") (pintype "passive"))
    )
    (net (code "17") (name "/LED1(PC13)") (class "Default")
      (node (ref "R54") (pin "2") (pinfunction "2_2") (pintype "passive"))
      (node (ref "U3") (pin "2") (pinfunction "PC13_2") (pintype "passive"))
    )
    (net (code "18") (name "/LED2(PC14)") (class "Default")
      (node (ref "R53") (pin "2") (pinfunction "2_2") (pintype "passive"))
      (node (ref "U3") (pin "3") (pinfunction "PC14/OSC32_IN_3") (pintype "passive"))
    )
    (net (code "19") (name "/RST") (class "Default")
      (node (ref "C18") (pin "1") (pinfunction "1_1") (pintype "passive"))
      (node (ref "KEY1") (pin "2") (pinfunction "2_2") (pintype "passive"))
      (node (ref "R43") (pin "1") (pinfunction "1_1") (pintype "passive"))
      (node (ref "T-RST") (pin "1") (pintype "passive"))
      (node (ref "U3") (pin "7") (pinfunction "NRST_7") (pintype "passive"))
    )
    (net (code "20") (name "/SWCLK") (class "Default")
      (node (ref "R30") (pin "1") (pinfunction "1_1") (pintype "passive"))
      (node (ref "U3") (pin "49") (pinfunction "PA14/JTCK/SWCLK_49") (pintype "passive"))
    )
    (net (code "21") (name "/SWDIO") (class "Default")
      (node (ref "R28") (pin "1") (pinfunction "1_1") (pintype "passive"))
      (node (ref "U3") (pin "46") (pinfunction "PA13/JTMS/SWDIO_46") (pintype "passive"))
    )
    (net (code "22") (name "/TIM2_CH1(PA15)") (class "Default")
      (node (ref "R32") (pin "1") (pinfunction "1_1") (pintype "passive"))
      (node (ref "U3") (pin "50") (pinfunction "PA15/JTDI_50") (pintype "passive"))
    )
    (net (code "23") (name "/TIM2_CH2(PB3)") (class "Default")
      (node (ref "R35") (pin "1") (pinfunction "1_1") (pintype "passive"))
      (node (ref "U3") (pin "55") (pinfunction "PB3/JTDO/TRACESWO_55") (pintype "passive"))
    )
    (net (code "24") (name "/TIM3_CH1(PB4)") (class "Default")
      (node (ref "R10") (pin "1") (pinfunction "1_1") (pintype "passive"))
      (node (ref "U3") (pin "56") (pinfunction "PB4/NJRST_56") (pintype "passive"))
    )
    (net (code "25") (name "/TIM3_CH2(PB5)") (class "Default")
      (node (ref "R11") (pin "1") (pinfunction "1_1") (pintype "passive"))
      (node (ref "U3") (pin "57") (pinfunction "PB5_57") (pintype "passive"))
    )
    (net (code "26") (name "/TIM3_CH3(PB0)") (class "Default")
      (node (ref "R12") (pin "1") (pinfunction "1_1") (pintype "passive"))
      (node (ref "U3") (pin "26") (pinfunction "PB0_26") (pintype "passive"))
    )
    (net (code "27") (name "/TIM3_CH4(PB1)") (class "Default")
      (node (ref "R17") (pin "1") (pinfunction "1_1") (pintype "passive"))
      (node (ref "U3") (pin "27") (pinfunction "PB1_27") (pintype "passive"))
    )
    (net (code "28") (name "/TIM8_CH3(PC8)") (class "Default")
      (node (ref "R39") (pin "1") (pinfunction "1_1") (pintype "passive"))
      (node (ref "U3") (pin "39") (pinfunction "PC8_39") (pintype "passive"))
    )
    (net (code "29") (name "/TIM8_CH4(PC9)") (class "Default")
      (node (ref "R37") (pin "1") (pinfunction "1_1") (pintype "passive"))
      (node (ref "U3") (pin "40") (pinfunction "PC9_40") (pintype "passive"))
    )
    (net (code "30") (name "/UART4_RX(PA1)") (class "Default")
      (node (ref "R24") (pin "1") (pinfunction "1_1") (pintype "passive"))
      (node (ref "U3") (pin "15") (pinfunction "PA1_15") (pintype "passive"))
    )
    (net (code "31") (name "/UART4_TX(PA0)") (class "Default")
      (node (ref "R25") (pin "1") (pinfunction "1_1") (pintype "passive"))
      (node (ref "U3") (pin "14") (pinfunction "PA0/WKUP_14") (pintype "passive"))
    )
    (net (code "32") (name "/USART1_RX(PA10)") (class "Default")
      (node (ref "R15") (pin "1") (pinfunction "1_1") (pintype "passive"))
      (node (ref "T-USART1_RX") (pin "1") (pintype "passive"))
      (node (ref "U3") (pin "43") (pinfunction "PA10_43") (pintype "passive"))
    )
    (net (code "33") (name "/USART1_TX(PA9)") (class "Default")
      (node (ref "R16") (pin "1") (pinfunction "1_1") (pintype "passive"))
      (node (ref "T-USART1_TX") (pin "1") (pintype "passive"))
      (node (ref "U3") (pin "42") (pinfunction "PA9_42") (pintype "passive"))
    )
    (net (code "34") (name "/USART2_RX(PA3)") (class "Default")
      (node (ref "Q4") (pin "3") (pinfunction "C_3") (pintype "passive"))
      (node (ref "R13") (pin "2") (pinfunction "2_2") (pintype "passive"))
      (node (ref "U3") (pin "17") (pinfunction "PA3_17") (pintype "passive"))
    )
    (net (code "35") (name "/USART3_RX(PB11)") (class "Default")
      (node (ref "R19") (pin "1") (pinfunction "1_1") (pintype "passive"))
      (node (ref "U3") (pin "30") (pinfunction "PB11_30") (pintype "passive"))
    )
    (net (code "36") (name "/USART3_TX(PB10)") (class "Default")
      (node (ref "R22") (pin "1") (pinfunction "1_1") (pintype "passive"))
      (node (ref "U3") (pin "29") (pinfunction "PB10_29") (pintype "passive"))
    )
    (net (code "37") (name "/USART6_RX(PC7)") (class "Default")
      (node (ref "R31") (pin "1") (pinfunction "1_1") (pintype "passive"))
      (node (ref "U3") (pin "38") (pinfunction "PC7_38") (pintype "passive"))
    )
    (net (code "38") (name "/USART6_TX(PC6)") (class "Default")
      (node (ref "R33") (pin "1") (pinfunction "1_1") (pintype "passive"))
      (node (ref "U3") (pin "37") (pinfunction "PC6_37") (pintype "passive"))
    )
    (net (code "39") (name "3.3V") (class "Default")
      (node (ref "C16") (pin "2") (pinfunction "2_2") (pintype "passive"))
      (node (ref "C17") (pin "2") (pinfunction "2_2") (pintype "passive"))
      (node (ref "C23") (pin "1") (pinfunction "1_1") (pintype "passive"))
      (node (ref "C24") (pin "1") (pinfunction "1_1") (pintype "passive"))
      (node (ref "C25") (pin "2") (pinfunction "2_2") (pintype "passive"))
      (node (ref "C31") (pin "1") (pinfunction "1_1") (pintype "passive"))
      (node (ref "CAN1") (pin "3") (pinfunction "VCC_3") (pintype "passive"))
      (node (ref "CAN2") (pin "3") (pinfunction "VCC_3") (pintype "passive"))
      (node (ref "D6") (pin "A") (pinfunction "A_A") (pintype "passive"))
      (node (ref "F2") (pin "1") (pinfunction "1_1") (pintype "passive"))
      (node (ref "J5") (pin "4") (pinfunction "4_4") (pintype "passive"))
      (node (ref "J6") (pin "4") (pinfunction "4_4") (pintype "passive"))
      (node (ref "LED1") (pin "A") (pinfunction "A_A") (pintype "passive"))
      (node (ref "LED2") (pin "A") (pinfunction "A_A") (pintype "passive"))
      (node (ref "R13") (pin "1") (pinfunction "1_1") (pintype "passive"))
      (node (ref "R18") (pin "2") (pinfunction "2_2") (pintype "passive"))
      (node (ref "R42") (pin "1") (pinfunction "1_1") (pintype "passive"))
      (node (ref "R43") (pin "2") (pinfunction "2_2") (pintype "passive"))
      (node (ref "U2") (pin "5") (pinfunction "OUT_5") (pintype "passive"))
      (node (ref "U3") (pin "13") (pinfunction "VDDA_13") (pintype "power_in"))
    )
    (net (code "40") (name "3.3V_SWD") (class "Default")
      (node (ref "F2") (pin "2") (pinfunction "2_2") (pintype "passive"))
      (node (ref "J4") (pin "4") (pinfunction "4_4") (pintype "passive"))
    )
    (net (code "41") (name "5V") (class "Default")
      (node (ref "C10") (pin "2") (pinfunction "2_2") (pintype "passive"))
      (node (ref "C11") (pin "2") (pinfunction "2_2") (pintype "passive"))
      (node (ref "C12") (pin "2") (pinfunction "2_2") (pintype "passive"))
      (node (ref "C14") (pin "1") (pinfunction "1_1") (pintype "passive"))
      (node (ref "C15") (pin "1") (pinfunction "1_1") (pintype "passive"))
      (node (ref "C34") (pin "2") (pinfunction "2_2") (pintype "passive"))
      (node (ref "D7") (pin "1") (pinfunction "C_1") (pintype "passive"))
      (node (ref "DBUS") (pin "2") (pinfunction "2_2") (pintype "passive"))
      (node (ref "F1") (pin "1") (pinfunction "1_1") (pintype "passive"))
      (node (ref "L1") (pin "2") (pinfunction "2_2") (pintype "passive"))
      (node (ref "PWM1") (pin "2") (pinfunction "2_2") (pintype "passive"))
      (node (ref "PWM2") (pin "2") (pinfunction "2_2") (pintype "passive"))
      (node (ref "PWM3") (pin "2") (pinfunction "2_2") (pintype "passive"))
      (node (ref "PWM4") (pin "2") (pinfunction "2_2") (pintype "passive"))
      (node (ref "PWM5") (pin "2") (pinfunction "2_2") (pintype "passive"))
      (node (ref "PWM6") (pin "2") (pinfunction "2_2") (pintype "passive"))
      (node (ref "PWM7") (pin "2") (pinfunction "2_2") (pintype "passive"))
      (node (ref "PWM8") (pin "2") (pinfunction "2_2") (pintype "passive"))
      (node (ref "R9") (pin "1") (pinfunction "1_1") (pintype "passive"))
      (node (ref "U2") (pin "1") (pinfunction "IN_1") (pintype "passive"))
      (node (ref "U2") (pin "3") (pinfunction "EN_3") (pintype "passive"))
    )
    (net (code "42") (name "5V_USART") (class "Default")
      (node (ref "F1") (pin "2") (pinfunction "2_2") (pintype "passive"))
      (node (ref "J10") (pin "4") (pinfunction "4_4") (pintype "passive"))
      (node (ref "J7") (pin "4") (pinfunction "4_4") (pintype "passive"))
      (node (ref "J8") (pin "4") (pinfunction "4_4") (pintype "passive"))
      (node (ref "J9") (pin "4") (pinfunction "4_4") (pintype "passive"))
    )
    (net (code "43") (name "24V") (class "Default")
      (node (ref "J1") (pin "1") (pinfunction "VCC_1") (pintype "passive"))
      (node (ref "J2") (pin "1") (pinfunction "VCC_1") (pintype "passive"))
      (node (ref "J3") (pin "1") (pinfunction "VCC_1") (pintype "passive"))
      (node (ref "P5") (pin "4") (pinfunction "VCC_4") (pintype "passive"))
      (node (ref "P5") (pin "5") (pinfunction "VCC_5") (pintype "passive"))
      (node (ref "P5") (pin "6") (pinfunction "VCC_6") (pintype "passive"))
      (node (ref "P6") (pin "4") (pinfunction "VCC_4") (pintype "passive"))
      (node (ref "P6") (pin "5") (pinfunction "VCC_5") (pintype "passive"))
      (node (ref "P6") (pin "6") (pinfunction "VCC_6") (pintype "passive"))
      (node (ref "Q1 PMOS") (pin "1") (pinfunction "S_1") (pintype "passive"))
      (node (ref "Q1 PMOS") (pin "2") (pinfunction "S_2") (pintype "passive"))
      (node (ref "Q1 PMOS") (pin "3") (pinfunction "S_3") (pintype "passive"))
      (node (ref "Q2") (pin "1") (pinfunction "E_1") (pintype "passive"))
      (node (ref "R2") (pin "2") (pinfunction "2_2") (pintype "passive"))
      (node (ref "R3") (pin "1") (pinfunction "1_1") (pintype "passive"))
      (node (ref "R50") (pin "2") (pinfunction "2_2") (pintype "passive"))
    )
    (net (code "44") (name "24V_OUT") (class "Default")
      (node (ref "3.3A") (pin "1") (pinfunction "1_1") (pintype "passive"))
      (node (ref "C1") (pin "2") (pinfunction "2_2") (pintype "passive"))
      (node (ref "C2") (pin "2") (pinfunction "2_2") (pintype "passive"))
      (node (ref "C3") (pin "1") (pinfunction "1_1") (pintype "passive"))
      (node (ref "C4") (pin "1") (pinfunction "1_1") (pintype "passive"))
      (node (ref "C5") (pin "1") (pinfunction "1_1") (pintype "passive"))
      (node (ref "D1") (pin "2") (pinfunction "2_2") (pintype "passive"))
      (node (ref "R8") (pin "2") (pinfunction "2_2") (pintype "passive"))
      (node (ref "U1") (pin "5") (pinfunction "VIN_5") (pintype "passive"))
    )
    (net (code "45") (name "AGND") (class "Default")
      (node (ref "C24") (pin "2") (pinfunction "2_2") (pintype "passive"))
      (node (ref "C25") (pin "1") (pinfunction "1_1") (pintype "passive"))
      (node (ref "R46") (pin "1") (pinfunction "1_1") (pintype "passive"))
      (node (ref "U3") (pin "12") (pinfunction "VSSA_12") (pintype "power_in"))
    )
    (net (code "46") (name "GND") (class "Default")
      (node (ref "C18") (pin "2") (pinfunction "2_2") (pintype "passive"))
      (node (ref "C19") (pin "1") (pinfunction "1_1") (pintype "passive"))
      (node (ref "C20") (pin "1") (pinfunction "1_1") (pintype "passive"))
      (node (ref "C21") (pin "1") (pinfunction "1_1") (pintype "passive"))
      (node (ref "C22") (pin "1") (pinfunction "1_1") (pintype "passive"))
      (node (ref "C23") (pin "2") (pinfunction "2_2") (pintype "passive"))
      (node (ref "C26") (pin "2") (pinfunction "2_2") (pintype "passive"))
      (node (ref "C27") (pin "1") (pinfunction "1_1") (pintype "passive"))
      (node (ref "C28") (pin "1") (pinfunction "1_1") (pintype "passive"))
      (node (ref "C29") (pin "2") (pinfunction "2_2") (pintype "passive"))
      (node (ref "C30") (pin "2") (pinfunction "2_2") (pintype "passive"))
      (node (ref "C31") (pin "2") (pinfunction "2_2") (pintype "passive"))
      (node (ref "C32") (pin "1") (pinfunction "1_1") (pintype "passive"))
      (node (ref "C33") (pin "1") (pinfunction "1_1") (pintype "passive"))
      (node (ref "CAN1") (pin "2") (pinfunction "GND_2") (pintype "passive"))
      (node (ref "CAN1") (pin "8") (pinfunction "RS_8") (pintype "passive"))
      (node (ref "CAN2") (pin "2") (pinfunction "GND_2") (pintype "passive"))
      (node (ref "CAN2") (pin "8") (pinfunction "RS_8") (pintype "passive"))
      (node (ref "D7") (pin "2") (pinfunction "A_2") (pintype "passive"))
      (node (ref "J10") (pin "3") (pinfunction "3_3") (pintype "passive"))
      (node (ref "J10") (pin "5") (pinfunction "5_5") (pintype "passive"))
      (node (ref "J10") (pin "6") (pinfunction "6_6") (pintype "passive"))
      (node (ref "J4") (pin "3") (pinfunction "3_3") (pintype "passive"))
      (node (ref "J4") (pin "5") (pinfunction "5_5") (pintype "passive"))
      (node (ref "J4") (pin "6") (pinfunction "6_6") (pintype "passive"))
      (node (ref "J5") (pin "3") (pinfunction "3_3") (pintype "passive"))
      (node (ref "J5") (pin "5") (pinfunction "5_5") (pintype "passive"))
      (node (ref "J5") (pin "6") (pinfunction "6_6") (pintype "passive"))
      (node (ref "J6") (pin "3") (pinfunction "3_3") (pintype "passive"))
      (node (ref "J6") (pin "5") (pinfunction "5_5") (pintype "passive"))
      (node (ref "J6") (pin "6") (pinfunction "6_6") (pintype "passive"))
      (node (ref "J7") (pin "3") (pinfunction "3_3") (pintype "passive"))
      (node (ref "J7") (pin "5") (pinfunction "5_5") (pintype "passive"))
      (node (ref "J7") (pin "6") (pinfunction "6_6") (pintype "passive"))
      (node (ref "J8") (pin "3") (pinfunction "3_3") (pintype "passive"))
      (node (ref "J8") (pin "5") (pinfunction "5_5") (pintype "passive"))
      (node (ref "J8") (pin "6") (pinfunction "6_6") (pintype "passive"))
      (node (ref "J9") (pin "3") (pinfunction "3_3") (pintype "passive"))
      (node (ref "J9") (pin "5") (pinfunction "5_5") (pintype "passive"))
      (node (ref "J9") (pin "6") (pinfunction "6_6") (pintype "passive"))
      (node (ref "KEY1") (pin "1") (pinfunction "1_1") (pintype "passive"))
      (node (ref "R23") (pin "1") (pinfunction "1_1") (pintype "passive"))
      (node (ref "R41") (pin "2") (pinfunction "2_2") (pintype "passive"))
      (node (ref "R44") (pin "2") (pinfunction "2_2") (pintype "passive"))
      (node (ref "R45") (pin "1") (pinfunction "1_1") (pintype "passive"))
      (node (ref "R47") (pin "1") (pinfunction "1_1") (pintype "passive"))
      (node (ref "T-GND1") (pin "1") (pintype "passive"))
      (node (ref "T-GND2") (pin "1") (pintype "passive"))
      (node (ref "T-GND3") (pin "1") (pintype "passive"))
      (node (ref "U3") (pin "18") (pinfunction "VSS_18") (pintype "power_in"))
      (node (ref "U3") (pin "63") (pinfunction "VSS_63") (pintype "power_in"))
    )
    (net (code "47") (name "IGND") (class "Default")
      (node (ref "C7") (pin "1") (pinfunction "1_1") (pintype "passive"))
      (node (ref "D2") (pin "2") (pinfunction "A_2") (pintype "passive"))
      (node (ref "J1") (pin "2") (pinfunction "GND_2") (pintype "passive"))
      (node (ref "J2") (pin "2") (pinfunction "GND_2") (pintype "passive"))
      (node (ref "J3") (pin "2") (pinfunction "GND_2") (pintype "passive"))
      (node (ref "P5") (pin "1") (pinfunction "GND_1") (pintype "passive"))
      (node (ref "P5") (pin "10") (pinfunction "GND_10") (pintype "passive"))
      (node (ref "P5") (pin "2") (pinfunction "GND_2") (pintype "passive"))
      (node (ref "P5") (pin "3") (pinfunction "GND_3") (pintype "passive"))
      (node (ref "P5") (pin "9") (pinfunction "GND_9") (pintype "passive"))
      (node (ref "P6") (pin "1") (pinfunction "GND_1") (pintype "passive"))
      (node (ref "P6") (pin "10") (pinfunction "GND_10") (pintype "passive"))
      (node (ref "P6") (pin "2") (pinfunction "GND_2") (pintype "passive"))
      (node (ref "P6") (pin "3") (pinfunction "GND_3") (pintype "passive"))
      (node (ref "P6") (pin "9") (pinfunction "GND_9") (pintype "passive"))
      (node (ref "Q3 NMOS") (pin "5") (pinfunction "D_5") (pintype "passive"))
      (node (ref "Q3 NMOS") (pin "6") (pinfunction "D_6") (pintype "passive"))
      (node (ref "Q3 NMOS") (pin "7") (pinfunction "D_7") (pintype "passive"))
      (node (ref "Q3 NMOS") (pin "8") (pinfunction "D_8") (pintype "passive"))
    )
    (net (code "48") (name "Net-(C6-Pad2)") (class "Default")
      (node (ref "C6") (pin "2") (pinfunction "2_2") (pintype "passive"))
      (node (ref "R51") (pin "1") (pinfunction "1_1") (pintype "passive"))
    )
    (net (code "49") (name "Net-(C7-Pad2)") (class "Default")
      (node (ref "C7") (pin "2") (pinfunction "2_2") (pintype "passive"))
      (node (ref "R50") (pin "1") (pinfunction "1_1") (pintype "passive"))
    )
    (net (code "50") (name "Net-(C27-Pad2)") (class "Default")
      (node (ref "C27") (pin "2") (pinfunction "2_2") (pintype "passive"))
      (node (ref "R18") (pin "1") (pinfunction "1_1") (pintype "passive"))
      (node (ref "R21") (pin "1") (pinfunction "1_1") (pintype "passive"))
      (node (ref "R23") (pin "2") (pinfunction "2_2") (pintype "passive"))
    )
    (net (code "51") (name "Net-(D2-K)") (class "Default")
      (node (ref "D2") (pin "1") (pinfunction "K_1") (pintype "passive"))
      (node (ref "R3") (pin "2") (pinfunction "2_2") (pintype "passive"))
      (node (ref "R4") (pin "1") (pinfunction "1_1") (pintype "passive"))
    )
    (net (code "52") (name "Net-(D3-A)") (class "Default")
      (node (ref "D3") (pin "2") (pinfunction "A_2") (pintype "passive"))
      (node (ref "Q1 PMOS") (pin "4") (pinfunction "G_4") (pintype "passive"))
      (node (ref "R5") (pin "2") (pinfunction "2_2") (pintype "passive"))
    )
    (net (code "53") (name "Net-(D3-C)") (class "Default")
      (node (ref "3.3A") (pin "2") (pinfunction "2_2") (pintype "passive"))
      (node (ref "D3") (pin "1") (pinfunction "C_1") (pintype "passive"))
      (node (ref "Q1 PMOS") (pin "5") (pinfunction "D_5") (pintype "passive"))
      (node (ref "Q1 PMOS") (pin "6") (pinfunction "D_6") (pintype "passive"))
      (node (ref "Q1 PMOS") (pin "7") (pinfunction "D_7") (pintype "passive"))
      (node (ref "Q1 PMOS") (pin "8") (pinfunction "D_8") (pintype "passive"))
      (node (ref "R1") (pin "2") (pinfunction "2_2") (pintype "passive"))
      (node (ref "R51") (pin "2") (pinfunction "2_2") (pintype "passive"))
    )
    (net (code "54") (name "Net-(D4-C)") (class "Default")
      (node (ref "D4") (pin "1") (pinfunction "C_1") (pintype "passive"))
      (node (ref "Q3 NMOS") (pin "4") (pinfunction "G_4") (pintype "passive"))
      (node (ref "R2") (pin "1") (pinfunction "1_1") (pintype "passive"))
    )
    (net (code "55") (name "Net-(D5-K)") (class "Default")
      (node (ref "C9") (pin "1") (pinfunction "1_1") (pintype "passive"))
      (node (ref "D5") (pin "1") (pinfunction "K_1") (pintype "passive"))
      (node (ref "L1") (pin "1") (pinfunction "1_1") (pintype "passive"))
      (node (ref "U1") (pin "6") (pinfunction "SW_6") (pintype "passive"))
    )
    (net (code "56") (name "Net-(D6-PadK)") (class "Default")
      (node (ref "D6") (pin "K") (pinfunction "K_K") (pintype "passive"))
      (node (ref "R41") (pin "1") (pinfunction "1_1") (pintype "passive"))
    )
    (net (code "57") (name "Net-(GPIO1-Pad1)") (class "Default")
      (node (ref "GPIO1") (pin "1") (pinfunction "1_1") (pintype "passive"))
      (node (ref "R26") (pin "2") (pinfunction "2_2") (pintype "passive"))
    )
    (net (code "58") (name "Net-(GPIO1-Pad2)") (class "Default")
      (node (ref "GPIO1") (pin "2") (pinfunction "2_2") (pintype "passive"))
      (node (ref "R29") (pin "2") (pinfunction "2_2") (pintype "passive"))
    )
    (net (code "59") (name "Net-(GPIO1-Pad3)") (class "Default")
      (node (ref "GPIO1") (pin "3") (pinfunction "3_3") (pintype "passive"))
      (node (ref "R34") (pin "2") (pinfunction "2_2") (pintype "passive"))
    )
    (net (code "60") (name "Net-(GPIO1-Pad4)") (class "Default")
      (node (ref "GPIO1") (pin "4") (pinfunction "4_4") (pintype "passive"))
      (node (ref "R36") (pin "2") (pinfunction "2_2") (pintype "passive"))
    )
    (net (code "61") (name "Net-(GPIO1-Pad5)") (class "Default")
      (node (ref "GPIO1") (pin "5") (pinfunction "5_5") (pintype "passive"))
      (node (ref "R38") (pin "2") (pinfunction "2_2") (pintype "passive"))
    )
    (net (code "62") (name "Net-(GPIO1-Pad6)") (class "Default")
      (node (ref "GPIO1") (pin "6") (pinfunction "6_6") (pintype "passive"))
      (node (ref "R40") (pin "2") (pinfunction "2_2") (pintype "passive"))
    )
    (net (code "63") (name "Net-(J4-Pad1)") (class "Default")
      (node (ref "J4") (pin "1") (pinfunction "1_1") (pintype "passive"))
      (node (ref "R28") (pin "2") (pinfunction "2_2") (pintype "passive"))
    )
    (net (code "64") (name "Net-(J4-Pad2)") (class "Default")
      (node (ref "J4") (pin "2") (pinfunction "2_2") (pintype "passive"))
      (node (ref "R30") (pin "2") (pinfunction "2_2") (pintype "passive"))
    )
    (net (code "65") (name "Net-(J7-Pad1)") (class "Default")
      (node (ref "J7") (pin "1") (pinfunction "1_1") (pintype "passive"))
      (node (ref "R16") (pin "2") (pinfunction "2_2") (pintype "passive"))
    )
    (net (code "66") (name "Net-(J7-Pad2)") (class "Default")
      (node (ref "J7") (pin "2") (pinfunction "2_2") (pintype "passive"))
      (node (ref "R15") (pin "2") (pinfunction "2_2") (pintype "passive"))
    )
    (net (code "67") (name "Net-(J8-Pad1)") (class "Default")
      (node (ref "J8") (pin "1") (pinfunction "1_1") (pintype "passive"))
      (node (ref "R22") (pin "2") (pinfunction "2_2") (pintype "passive"))
    )
    (net (code "68") (name "Net-(J8-Pad2)") (class "Default")
      (node (ref "J8") (pin "2") (pinfunction "2_2") (pintype "passive"))
      (node (ref "R19") (pin "2") (pinfunction "2_2") (pintype "passive"))
    )
    (net (code "69") (name "Net-(J9-Pad1)") (class "Default")
      (node (ref "J9") (pin "1") (pinfunction "1_1") (pintype "passive"))
      (node (ref "R25") (pin "2") (pinfunction "2_2") (pintype "passive"))
    )
    (net (code "70") (name "Net-(J9-Pad2)") (class "Default")
      (node (ref "J9") (pin "2") (pinfunction "2_2") (pintype "passive"))
      (node (ref "R24") (pin "2") (pinfunction "2_2") (pintype "passive"))
    )
    (net (code "71") (name "Net-(J10-Pad1)") (class "Default")
      (node (ref "J10") (pin "1") (pinfunction "1_1") (pintype "passive"))
      (node (ref "R33") (pin "2") (pinfunction "2_2") (pintype "passive"))
    )
    (net (code "72") (name "Net-(J10-Pad2)") (class "Default")
      (node (ref "J10") (pin "2") (pinfunction "2_2") (pintype "passive"))
      (node (ref "R31") (pin "2") (pinfunction "2_2") (pintype "passive"))
    )
    (net (code "73") (name "Net-(LED1-PadK)") (class "Default")
      (node (ref "LED1") (pin "K") (pinfunction "K_K") (pintype "passive"))
      (node (ref "R54") (pin "1") (pinfunction "1_1") (pintype "passive"))
    )
    (net (code "74") (name "Net-(LED2-PadK)") (class "Default")
      (node (ref "LED2") (pin "K") (pinfunction "K_K") (pintype "passive"))
      (node (ref "R53") (pin "1") (pinfunction "1_1") (pintype "passive"))
    )
    (net (code "75") (name "Net-(PWM1-Pad1)") (class "Default")
      (node (ref "PWM1") (pin "1") (pinfunction "1_1") (pintype "passive"))
      (node (ref "R10") (pin "2") (pinfunction "2_2") (pintype "passive"))
    )
    (net (code "76") (name "Net-(PWM2-Pad1)") (class "Default")
      (node (ref "PWM2") (pin "1") (pinfunction "1_1") (pintype "passive"))
      (node (ref "R11") (pin "2") (pinfunction "2_2") (pintype "passive"))
    )
    (net (code "77") (name "Net-(PWM3-Pad1)") (class "Default")
      (node (ref "PWM3") (pin "1") (pinfunction "1_1") (pintype "passive"))
      (node (ref "R12") (pin "2") (pinfunction "2_2") (pintype "passive"))
    )
    (net (code "78") (name "Net-(PWM4-Pad1)") (class "Default")
      (node (ref "PWM4") (pin "1") (pinfunction "1_1") (pintype "passive"))
      (node (ref "R17") (pin "2") (pinfunction "2_2") (pintype "passive"))
    )
    (net (code "79") (name "Net-(PWM5-Pad1)") (class "Default")
      (node (ref "PWM5") (pin "1") (pinfunction "1_1") (pintype "passive"))
      (node (ref "R32") (pin "2") (pinfunction "2_2") (pintype "passive"))
    )
    (net (code "80") (name "Net-(PWM6-Pad1)") (class "Default")
      (node (ref "PWM6") (pin "1") (pinfunction "1_1") (pintype "passive"))
      (node (ref "R35") (pin "2") (pinfunction "2_2") (pintype "passive"))
    )
    (net (code "81") (name "Net-(PWM7-Pad1)") (class "Default")
      (node (ref "PWM7") (pin "1") (pinfunction "1_1") (pintype "passive"))
      (node (ref "R37") (pin "2") (pinfunction "2_2") (pintype "passive"))
    )
    (net (code "82") (name "Net-(PWM8-Pad1)") (class "Default")
      (node (ref "PWM8") (pin "1") (pinfunction "1_1") (pintype "passive"))
      (node (ref "R39") (pin "2") (pinfunction "2_2") (pintype "passive"))
    )
    (net (code "83") (name "Net-(Q2-B)") (class "Default")
      (node (ref "C8") (pin "2") (pinfunction "2_2") (pintype "passive"))
      (node (ref "Q2") (pin "2") (pinfunction "B_2") (pintype "passive"))
      (node (ref "R1") (pin "1") (pinfunction "1_1") (pintype "passive"))
      (node (ref "R4") (pin "2") (pinfunction "2_2") (pintype "passive"))
    )
    (net (code "84") (name "Net-(Q2-C)") (class "Default")
      (node (ref "C8") (pin "1") (pinfunction "1_1") (pintype "passive"))
      (node (ref "Q2") (pin "3") (pinfunction "C_3") (pintype "passive"))
      (node (ref "R5") (pin "1") (pinfunction "1_1") (pintype "passive"))
      (node (ref "R6") (pin "2") (pinfunction "2_2") (pintype "passive"))
    )
    (net (code "85") (name "Net-(Q4-B)") (class "Default")
      (node (ref "Q4") (pin "2") (pinfunction "B_2") (pintype "passive"))
      (node (ref "R14") (pin "1") (pinfunction "1_1") (pintype "passive"))
    )
    (net (code "86") (name "Net-(U1-BST)") (class "Default")
      (node (ref "C9") (pin "2") (pinfunction "2_2") (pintype "passive"))
      (node (ref "U1") (pin "1") (pinfunction "BST_1") (pintype "passive"))
    )
    (net (code "87") (name "Net-(U1-EN)") (class "Default")
      (node (ref "R8") (pin "1") (pinfunction "1_1") (pintype "passive"))
      (node (ref "U1") (pin "4") (pinfunction "EN_4") (pintype "passive"))
    )
    (net (code "88") (name "Net-(U1-FB)") (class "Default")
      (node (ref "C14") (pin "2") (pinfunction "2_2") (pintype "passive"))
      (node (ref "R7") (pin "2") (pinfunction "2_2") (pintype "passive"))
      (node (ref "R9") (pin "2") (pinfunction "2_2") (pintype "passive"))
      (node (ref "U1") (pin "3") (pinfunction "FB_3") (pintype "passive"))
    )
    (net (code "89") (name "Net-(U2-BYT)") (class "Default")
      (node (ref "C40") (pin "1") (pinfunction "1_1") (pintype "passive"))
      (node (ref "U2") (pin "4") (pinfunction "BYT_4") (pintype "passive"))
    )
    (net (code "90") (name "Net-(U3-BOOT0)") (class "Default")
      (node (ref "R44") (pin "1") (pinfunction "1_1") (pintype "passive"))
      (node (ref "T-BOOT0") (pin "1") (pintype "passive"))
      (node (ref "U3") (pin "60") (pinfunction "BOOT0_60") (pintype "passive"))
    )
    (net (code "91") (name "Net-(U3-PB2{slash}BOOT1)") (class "Default")
      (node (ref "R45") (pin "2") (pinfunction "2_2") (pintype "passive"))
      (node (ref "T-BOOT1") (pin "1") (pintype "passive"))
      (node (ref "U3") (pin "28") (pinfunction "PB2/BOOT1_28") (pintype "passive"))
    )
    (net (code "92") (name "Net-(U3-PH0{slash}OSC_IN)") (class "Default")
      (node (ref "C21") (pin "2") (pinfunction "2_2") (pintype "passive"))
      (node (ref "U3") (pin "5") (pinfunction "PH0/OSC_IN_5") (pintype "passive"))
      (node (ref "Y1") (pin "3") (pinfunction "OSC2_3") (pintype "passive"))
    )
    (net (code "93") (name "Net-(U3-PH1{slash}OSC_OUT)") (class "Default")
      (node (ref "C22") (pin "2") (pinfunction "2_2") (pintype "passive"))
      (node (ref "U3") (pin "6") (pinfunction "PH1/OSC_OUT_6") (pintype "passive"))
      (node (ref "Y1") (pin "1") (pinfunction "OSC1_1") (pintype "passive"))
    )
    (net (code "94") (name "Net-(U3-VCAP_1)") (class "Default")
      (node (ref "C32") (pin "2") (pinfunction "2_2") (pintype "passive"))
      (node (ref "U3") (pin "31") (pinfunction "VCAP_1_31") (pintype "passive"))
    )
    (net (code "95") (name "Net-(U3-VCAP_2)") (class "Default")
      (node (ref "C30") (pin "1") (pinfunction "1_1") (pintype "passive"))
      (node (ref "U3") (pin "47") (pinfunction "VCAP_2_47") (pintype "passive"))
    )
    (net (code "96") (name "PGND") (class "Default")
      (node (ref "C1") (pin "1") (pinfunction "1_1") (pintype "passive"))
      (node (ref "C10") (pin "1") (pinfunction "1_1") (pintype "passive"))
      (node (ref "C11") (pin "1") (pinfunction "1_1") (pintype "passive"))
      (node (ref "C12") (pin "1") (pinfunction "1_1") (pintype "passive"))
      (node (ref "C15") (pin "2") (pinfunction "2_2") (pintype "passive"))
      (node (ref "C16") (pin "1") (pinfunction "1_1") (pintype "passive"))
      (node (ref "C17") (pin "1") (pinfunction "1_1") (pintype "passive"))
      (node (ref "C2") (pin "1") (pinfunction "1_1") (pintype "passive"))
      (node (ref "C3") (pin "2") (pinfunction "2_2") (pintype "passive"))
      (node (ref "C34") (pin "1") (pinfunction "1_1") (pintype "passive"))
      (node (ref "C4") (pin "2") (pinfunction "2_2") (pintype "passive"))
      (node (ref "C40") (pin "2") (pinfunction "2_2") (pintype "passive"))
      (node (ref "C5") (pin "2") (pinfunction "2_2") (pintype "passive"))
      (node (ref "C6") (pin "1") (pinfunction "1_1") (pintype "passive"))
      (node (ref "D1") (pin "1") (pinfunction "1_1") (pintype "passive"))
      (node (ref "D4") (pin "2") (pinfunction "A_2") (pintype "passive"))
      (node (ref "D5") (pin "2") (pinfunction "A_2") (pintype "passive"))
      (node (ref "DBUS") (pin "1") (pinfunction "1_1") (pintype "passive"))
      (node (ref "PWM1") (pin "3") (pinfunction "3_3") (pintype "passive"))
      (node (ref "PWM2") (pin "3") (pinfunction "3_3") (pintype "passive"))
      (node (ref "PWM3") (pin "3") (pinfunction "3_3") (pintype "passive"))
      (node (ref "PWM4") (pin "3") (pinfunction "3_3") (pintype "passive"))
      (node (ref "PWM5") (pin "3") (pinfunction "3_3") (pintype "passive"))
      (node (ref "PWM6") (pin "3") (pinfunction "3_3") (pintype "passive"))
      (node (ref "PWM7") (pin "3") (pinfunction "3_3") (pintype "passive"))
      (node (ref "PWM8") (pin "3") (pinfunction "3_3") (pintype "passive"))
      (node (ref "Q3 NMOS") (pin "1") (pinfunction "S_1") (pintype "passive"))
      (node (ref "Q3 NMOS") (pin "2") (pinfunction "S_2") (pintype "passive"))
      (node (ref "Q3 NMOS") (pin "3") (pinfunction "S_3") (pintype "passive"))
      (node (ref "Q4") (pin "1") (pinfunction "E_1") (pintype "passive"))
      (node (ref "R46") (pin "2") (pinfunction "2_2") (pintype "passive"))
      (node (ref "R47") (pin "2") (pinfunction "2_2") (pintype "passive"))
      (node (ref "R6") (pin "1") (pinfunction "1_1") (pintype "passive"))
      (node (ref "R7") (pin "1") (pinfunction "1_1") (pintype "passive"))
      (node (ref "U1") (pin "2") (pinfunction "GND_2") (pintype "passive"))
      (node (ref "U2") (pin "2") (pinfunction "GND_2") (pintype "passive"))
    )
    (net (code "97") (name "VDD") (class "Default")
      (node (ref "C19") (pin "2") (pinfunction "2_2") (pintype "passive"))
      (node (ref "C20") (pin "2") (pinfunction "2_2") (pintype "passive"))
      (node (ref "C26") (pin "1") (pinfunction "1_1") (pintype "passive"))
      (node (ref "C28") (pin "2") (pinfunction "2_2") (pintype "passive"))
      (node (ref "C29") (pin "1") (pinfunction "1_1") (pintype "passive"))
      (node (ref "C33") (pin "2") (pinfunction "2_2") (pintype "passive"))
      (node (ref "R42") (pin "2") (pinfunction "2_2") (pintype "passive"))
      (node (ref "T-1") (pin "1") (pintype "passive"))
      (node (ref "U3") (pin "1") (pinfunction "VBAT_1") (pintype "power_in"))
      (node (ref "U3") (pin "19") (pinfunction "VDD_19") (pintype "power_in"))
      (node (ref "U3") (pin "32") (pinfunction "VDD_32") (pintype "power_in"))
      (node (ref "U3") (pin "48") (pinfunction "VDD_48") (pintype "power_in"))
      (node (ref "U3") (pin "64") (pinfunction "VDD_64") (pintype "power_in"))
    )
    (net (code "98") (name "unconnected-(CAN1-LBK-Pad5)") (class "Default")
      (node (ref "CAN1") (pin "5") (pinfunction "LBK_5") (pintype "passive+no_connect"))
    )
    (net (code "99") (name "unconnected-(CAN2-LBK-Pad5)") (class "Default")
      (node (ref "CAN2") (pin "5") (pinfunction "LBK_5") (pintype "passive+no_connect"))
    )
    (net (code "100") (name "unconnected-(U3-PA2-Pad16)") (class "Default")
      (node (ref "U3") (pin "16") (pinfunction "PA2_16") (pintype "passive"))
    )
    (net (code "101") (name "unconnected-(U3-PA8-Pad41)") (class "Default")
      (node (ref "U3") (pin "41") (pinfunction "PA8_41") (pintype "passive"))
    )
    (net (code "102") (name "unconnected-(U3-PB6-Pad58)") (class "Default")
      (node (ref "U3") (pin "58") (pinfunction "PB6_58") (pintype "passive"))
    )
    (net (code "103") (name "unconnected-(U3-PB7-Pad59)") (class "Default")
      (node (ref "U3") (pin "59") (pinfunction "PB7_59") (pintype "passive"))
    )
    (net (code "104") (name "unconnected-(U3-PB8-Pad61)") (class "Default")
      (node (ref "U3") (pin "61") (pinfunction "PB8_61") (pintype "passive"))
    )
    (net (code "105") (name "unconnected-(U3-PB9-Pad62)") (class "Default")
      (node (ref "U3") (pin "62") (pinfunction "PB9_62") (pintype "passive"))
    )
    (net (code "106") (name "unconnected-(U3-PB14-Pad35)") (class "Default")
      (node (ref "U3") (pin "35") (pinfunction "PB14_35") (pintype "passive"))
    )
    (net (code "107") (name "unconnected-(U3-PB15-Pad36)") (class "Default")
      (node (ref "U3") (pin "36") (pinfunction "PB15_36") (pintype "passive"))
    )
    (net (code "108") (name "unconnected-(U3-PC0-Pad8)") (class "Default")
      (node (ref "U3") (pin "8") (pinfunction "PC0_8") (pintype "passive"))
    )
    (net (code "109") (name "unconnected-(U3-PC2-Pad10)") (class "Default")
      (node (ref "U3") (pin "10") (pinfunction "PC2_10") (pintype "passive"))
    )
    (net (code "110") (name "unconnected-(U3-PC3-Pad11)") (class "Default")
      (node (ref "U3") (pin "11") (pinfunction "PC3_11") (pintype "passive"))
    )
    (net (code "111") (name "unconnected-(U3-PC10-Pad51)") (class "Default")
      (node (ref "U3") (pin "51") (pinfunction "PC10_51") (pintype "passive"))
    )
    (net (code "112") (name "unconnected-(U3-PC11-Pad52)") (class "Default")
      (node (ref "U3") (pin "52") (pinfunction "PC11_52") (pintype "passive"))
    )
    (net (code "113") (name "unconnected-(U3-PC12-Pad53)") (class "Default")
      (node (ref "U3") (pin "53") (pinfunction "PC12_53") (pintype "passive"))
    )
    (net (code "114") (name "unconnected-(U3-PC15{slash}OSC32_OUT-Pad4)") (class "Default")
      (node (ref "U3") (pin "4") (pinfunction "PC15/OSC32_OUT_4") (pintype "passive"))
    )
    (net (code "115") (name "unconnected-(U3-PD2-Pad54)") (class "Default")
      (node (ref "U3") (pin "54") (pinfunction "PD2_54") (pintype "passive"))
    )
  )
)
